# CAN_Switch.net
KiCad netlist of a schematic drawn in Altium Designer
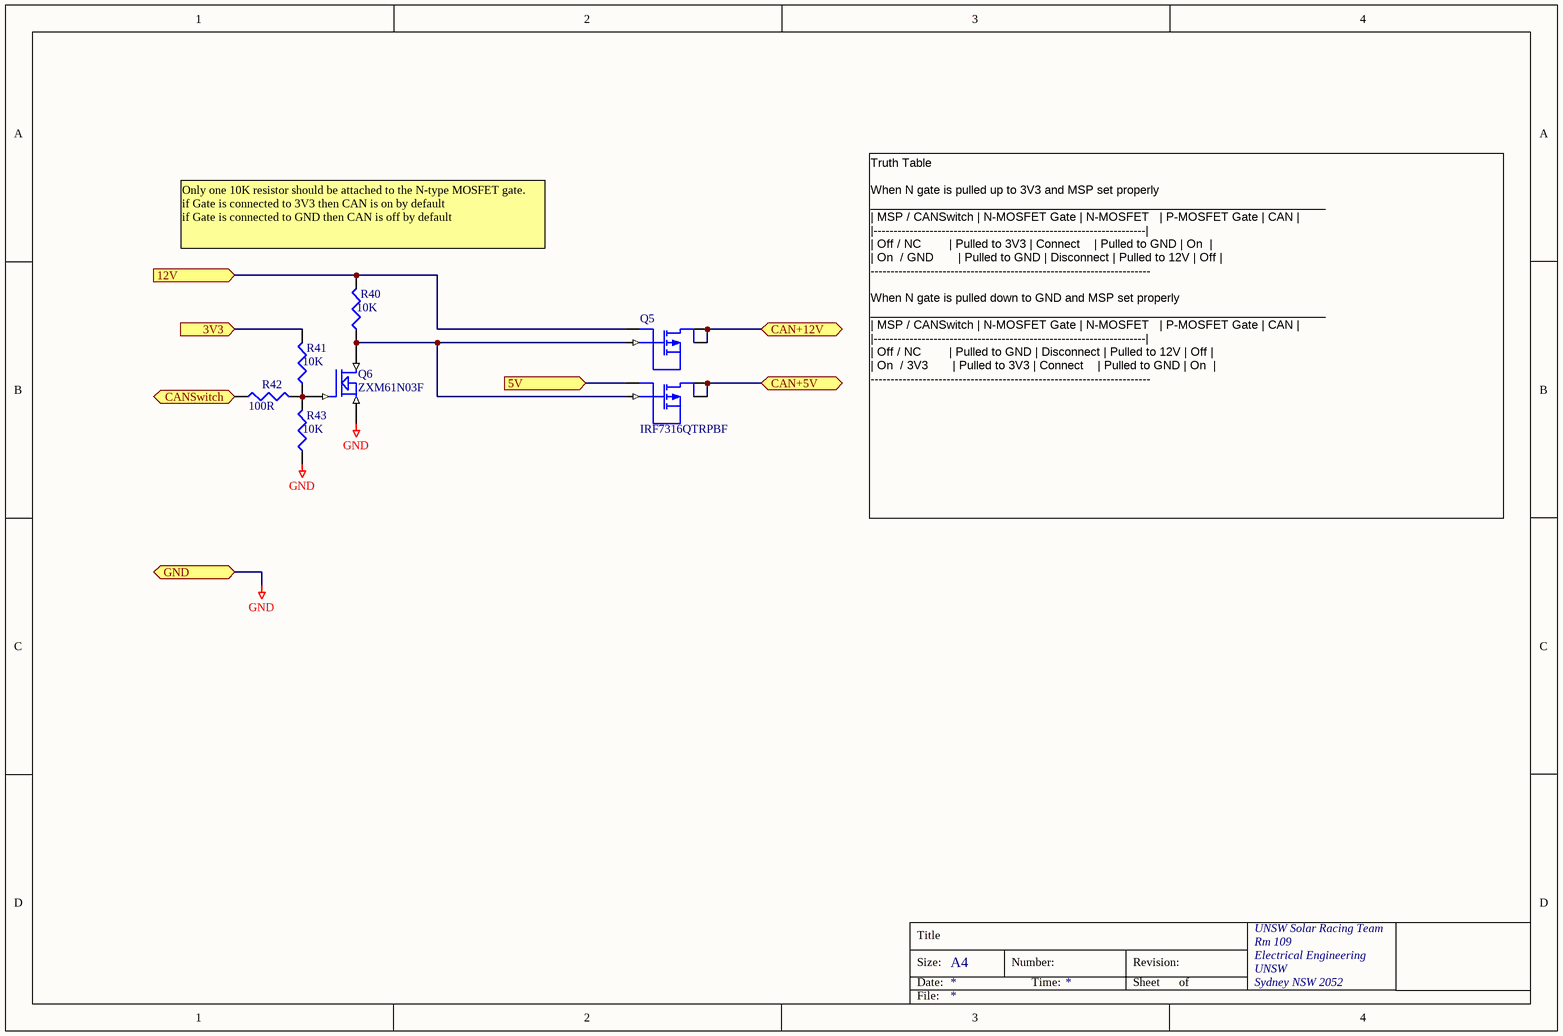
[diagram p0: CAN_Switch.SCHDOC]

(export (version "E")
  (design (tool "Eeschema 10.0.6"))
  (components
    (comp (ref "Q5")
      (value "IRF7316QTRPBF")
      (footprint "SO8")
      (description "Dual P-type MOSFET IC")
      (libsource (lib "RCLDQ") (part "IRF7316QTRPBF"))
    )
    (comp (ref "Q6")
      (value "ZXM61N03F")
      (footprint "SOT23-3")
      (description "1.7A, 20V N-Channel Enhancement mode FET")
      (libsource (lib "RCLDQ") (part "ZXM61N02F"))
    )
    (comp (ref "R40")
      (value "10K")
      (footprint "0603")
      (description "Resistor")
      (libsource (lib "*") (part "RES1"))
    )
    (comp (ref "R41")
      (value "10K")
      (footprint "0603")
      (description "Resistor")
      (libsource (lib "*") (part "RES1"))
    )
    (comp (ref "R42") (value "100R") (footprint "0603") (libsource (lib "RCLDQ") (part "RES1")))
    (comp (ref "R43")
      (value "10K")
      (footprint "0603")
      (description "Resistor")
      (libsource (lib "*") (part "RES1"))
    )
  )
  (nets
    (net (code "1") (name "/3V3") (class "Default")
      (node (ref "R41") (pin "2") (pinfunction "2_2") (pintype "passive"))
    )
    (net (code "2") (name "/5V") (class "Default")
      (node (ref "Q5") (pin "3") (pinfunction "S2_3") (pintype "bidirectional"))
    )
    (net (code "3") (name "/12V") (class "Default")
      (node (ref "Q5") (pin "1") (pinfunction "S1_1") (pintype "bidirectional"))
      (node (ref "R40") (pin "2") (pinfunction "2_2") (pintype "passive"))
    )
    (net (code "4") (name "/CAN+5V") (class "Default")
      (node (ref "Q5") (pin "5") (pinfunction "D2_5") (pintype "bidirectional"))
      (node (ref "Q5") (pin "6") (pinfunction "D2_6") (pintype "bidirectional"))
    )
    (net (code "5") (name "/CAN+12V") (class "Default")
      (node (ref "Q5") (pin "7") (pinfunction "D1_7") (pintype "bidirectional"))
      (node (ref "Q5") (pin "8") (pinfunction "D1_8") (pintype "bidirectional"))
    )
    (net (code "6") (name "/CANSwitch") (class "Default")
      (node (ref "R42") (pin "1") (pinfunction "1_1") (pintype "passive"))
    )
    (net (code "7") (name "GND") (class "Default")
      (node (ref "Q6") (pin "2") (pinfunction "S_2") (pintype "input"))
      (node (ref "R43") (pin "1") (pinfunction "1_1") (pintype "passive"))
    )
    (net (code "8") (name "Net-(Q5-G1)") (class "Default")
      (node (ref "Q5") (pin "2") (pinfunction "G1_2") (pintype "input"))
      (node (ref "Q5") (pin "4") (pinfunction "G2_4") (pintype "input"))
      (node (ref "Q6") (pin "3") (pinfunction "D_3") (pintype "input"))
      (node (ref "R40") (pin "1") (pinfunction "1_1") (pintype "passive"))
    )
    (net (code "9") (name "Net-(Q6-G)") (class "Default")
      (node (ref "Q6") (pin "1") (pinfunction "G_1") (pintype "input"))
      (node (ref "R41") (pin "1") (pinfunction "1_1") (pintype "passive"))
      (node (ref "R42") (pin "2") (pinfunction "2_2") (pintype "passive"))
      (node (ref "R43") (pin "2") (pinfunction "2_2") (pintype "passive"))
    )
  )
)
